# Power_Supply.net
KiCad netlist of a schematic drawn in Altium Designer
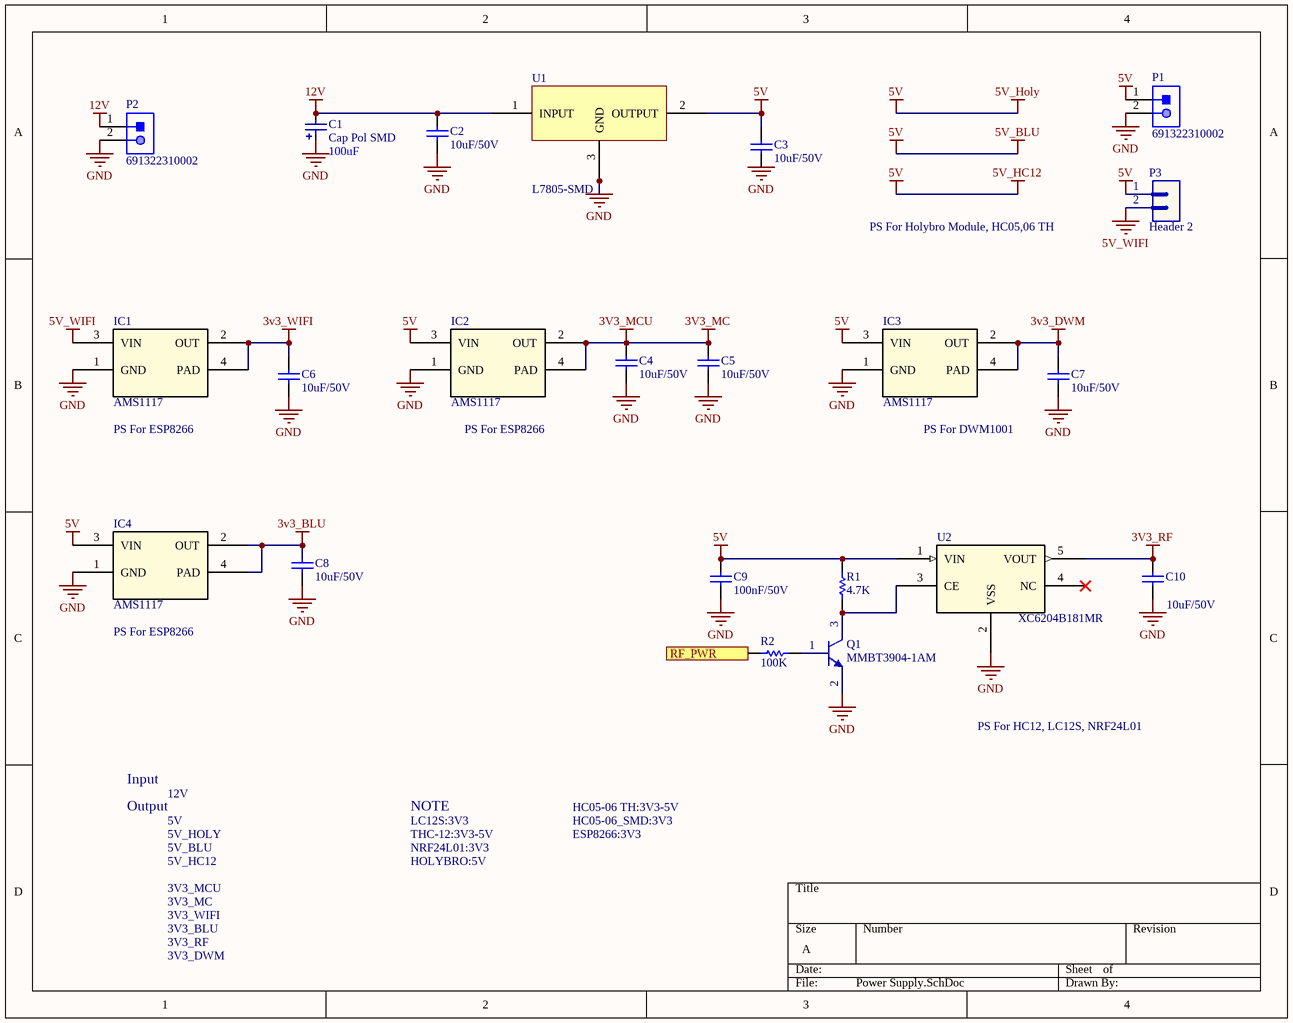
[diagram p0: Power Supply.SchDoc]

(export (version "E")
  (design (tool "Eeschema 10.0.6"))
  (components
    (comp (ref "C1")
      (value "Cap Pol SMD")
      (footprint "CAP ALU SIZE B")
      (description "Polarized Capacitor (Radial)")
      (fields (field (name "ALTIUM_VALUE") "100uF"))
      (libsource (lib "PIF_C16_lib") (part "Cap Pol SMD"))
    )
    (comp (ref "C2")
      (value "10uF/50V")
      (footprint "CAP-SM-0805")
      (description "CAP CER 10UF 50V X5R 0805")
      (fields
        (field (name "MANUFACTURER") "Yageo")
        (field (name "MANUFACTURER PART NUMBER") "CC0805KKX5R9BB106")
      )
      (libsource (lib "Capacitor") (part "Cap-10uF-50V-0805"))
    )
    (comp (ref "C3")
      (value "10uF/50V")
      (footprint "CAP-SM-0805")
      (description "CAP CER 10UF 50V X5R 0805")
      (fields
        (field (name "MANUFACTURER") "Yageo")
        (field (name "MANUFACTURER PART NUMBER") "CC0805KKX5R9BB106")
      )
      (libsource (lib "Capacitor") (part "Cap-10uF-50V-0805"))
    )
    (comp (ref "C4")
      (value "10uF/50V")
      (footprint "CAP-SM-0805")
      (description "CAP CER 10UF 50V X5R 0805")
      (fields
        (field (name "MANUFACTURER") "Yageo")
        (field (name "MANUFACTURER PART NUMBER") "CC0805KKX5R9BB106")
      )
      (libsource (lib "Capacitor") (part "Cap-10uF-50V-0805"))
    )
    (comp (ref "C5")
      (value "10uF/50V")
      (footprint "CAP-SM-0805")
      (description "CAP CER 10UF 50V X5R 0805")
      (fields
        (field (name "MANUFACTURER") "Yageo")
        (field (name "MANUFACTURER PART NUMBER") "CC0805KKX5R9BB106")
      )
      (libsource (lib "Capacitor") (part "Cap-10uF-50V-0805"))
    )
    (comp (ref "C6")
      (value "10uF/50V")
      (footprint "CAP-SM-0805")
      (description "CAP CER 10UF 50V X5R 0805")
      (fields
        (field (name "MANUFACTURER") "Yageo")
        (field (name "MANUFACTURER PART NUMBER") "CC0805KKX5R9BB106")
      )
      (libsource (lib "Capacitor") (part "Cap-10uF-50V-0805"))
    )
    (comp (ref "C7")
      (value "10uF/50V")
      (footprint "CAP-SM-0805")
      (description "CAP CER 10UF 50V X5R 0805")
      (fields
        (field (name "MANUFACTURER") "Yageo")
        (field (name "MANUFACTURER PART NUMBER") "CC0805KKX5R9BB106")
      )
      (libsource (lib "Capacitor") (part "Cap-10uF-50V-0805"))
    )
    (comp (ref "C8")
      (value "10uF/50V")
      (footprint "CAP-SM-0805")
      (description "CAP CER 10UF 50V X5R 0805")
      (fields
        (field (name "MANUFACTURER") "Yageo")
        (field (name "MANUFACTURER PART NUMBER") "CC0805KKX5R9BB106")
      )
      (libsource (lib "Capacitor") (part "Cap-10uF-50V-0805"))
    )
    (comp (ref "C9")
      (value "100nF/50V")
      (footprint "CAP-SM-0805")
      (description "CAP CER 0.1UF 50V Y5V 0805")
      (fields
        (field (name "MANUFACTURER") "Samsung Electro-Mechanics")
        (field (name "MANUFACTURER PART NUMBER") "CL21F104ZBCNNNC")
      )
      (libsource (lib "Capacitor") (part "Cap-100nF-50V-0805"))
    )
    (comp (ref "C10")
      (value "10uF/50V")
      (footprint "CAP-SM-0805")
      (description "CAP CER 10UF 50V X5R 0805")
      (fields
        (field (name "MANUFACTURER") "Yageo")
        (field (name "MANUFACTURER PART NUMBER") "CC0805KKX5R9BB106")
      )
      (libsource (lib "Capacitor") (part "Cap-10uF-50V-0805"))
    )
    (comp (ref "IC1")
      (value "AMS1117")
      (footprint "AMS1117")
      (fields (field (name "COPYRIGHT") "Copyright (C) 2018 Accelerated Designs. All rights reserved"))
      (libsource (lib "Integrated_Library") (part "AMS1117"))
    )
    (comp (ref "IC2")
      (value "AMS1117")
      (footprint "AMS1117")
      (fields (field (name "COPYRIGHT") "Copyright (C) 2018 Accelerated Designs. All rights reserved"))
      (libsource (lib "Integrated_Library") (part "AMS1117"))
    )
    (comp (ref "IC3")
      (value "AMS1117")
      (footprint "AMS1117")
      (fields (field (name "COPYRIGHT") "Copyright (C) 2018 Accelerated Designs. All rights reserved"))
      (libsource (lib "Integrated_Library") (part "AMS1117"))
    )
    (comp (ref "IC4")
      (value "AMS1117")
      (footprint "AMS1117")
      (fields (field (name "COPYRIGHT") "Copyright (C) 2018 Accelerated Designs. All rights reserved"))
      (libsource (lib "Integrated_Library") (part "AMS1117"))
    )
    (comp (ref "P1")
      (value "691322310002")
      (footprint "691322310002")
      (description "WR-TBL Serie 322 Horizontal PCB Header, Pluggable, pitch 3.81mm, 2p")
      (fields (field (name "PUBLISHER") "Wurth Elektronik"))
      (libsource (lib "691101710002_Altium_WR-TBL_rev19a") (part "691322310002"))
    )
    (comp (ref "P2")
      (value "691322310002")
      (footprint "691322310002")
      (description "WR-TBL Serie 322 Horizontal PCB Header, Pluggable, pitch 3.81mm, 2p")
      (fields (field (name "PUBLISHER") "Wurth Elektronik"))
      (libsource (lib "691101710002_Altium_WR-TBL_rev19a") (part "691322310002"))
    )
    (comp (ref "P3")
      (value "Header 2")
      (footprint "JP2")
      (description "Header, 2-Pin")
      (fields (field (name "PUBLISHER") "Altium Limited"))
      (libsource (lib "PIF_C16_lib") (part "Header 2"))
    )
    (comp (ref "Q1")
      (value "MMBT3904-1AM")
      (footprint "SOT23_NEX")
      (libsource (lib "BJT") (part "MMBT3904-1AM"))
    )
    (comp (ref "R1")
      (value "4.7K")
      (footprint "Resistor:RES-SM-0805")
      (description "RES 1K OHM 1% 1/4W 0805")
      (fields
        (field (name "MANUFACTURER") "Stackpole Electronics Inc")
        (field (name "MANUFACTURER PART NUMBER") "RNCP0805FTD1K00")
      )
      (libsource (lib "Resistor") (part "Res-1K-0805"))
    )
    (comp (ref "R2")
      (value "100K")
      (footprint "Resistor:RES-SM-0805")
      (description "RES 1K OHM 1% 1/4W 0805")
      (fields
        (field (name "MANUFACTURER") "Stackpole Electronics Inc")
        (field (name "MANUFACTURER PART NUMBER") "RNCP0805FTD1K00")
      )
      (libsource (lib "Resistor") (part "Res-1K-0805"))
    )
    (comp (ref "U1")
      (value "L7805-SMD")
      (footprint "L7805-SMD")
      (libsource (lib "Integrated_Library") (part "L7805-SMD"))
    )
    (comp (ref "U2")
      (value "XC6204B181MR")
      (footprint "XC6204B332MR")
      (fields (field (name "COPYRIGHT") "Copyright (C) 2018 Accelerated Designs. All rights reserved"))
      (libsource (lib "Integrated_Library") (part "XC6204B181MR"))
    )
  )
  (nets
    (net (code "1") (name "/RF_PWR") (class "Default")
      (node (ref "R2") (pin "2") (pinfunction "2_2") (pintype "passive"))
    )
    (net (code "2") (name "3V3_MC") (class "Default")
      (node (ref "C4") (pin "2") (pinfunction "2_2") (pintype "passive"))
      (node (ref "C5") (pin "2") (pinfunction "2_2") (pintype "passive"))
      (node (ref "IC2") (pin "2") (pinfunction "OUT_2") (pintype "open_collector"))
      (node (ref "IC2") (pin "4") (pinfunction "PAD_4") (pintype "power_in"))
    )
    (net (code "3") (name "3V3_RF") (class "Default")
      (node (ref "C10") (pin "2") (pinfunction "2_2") (pintype "passive"))
      (node (ref "U2") (pin "5") (pinfunction "VOUT_5") (pintype "output"))
    )
    (net (code "4") (name "3v3_BLU") (class "Default")
      (node (ref "C8") (pin "2") (pinfunction "2_2") (pintype "passive"))
      (node (ref "IC4") (pin "2") (pinfunction "OUT_2") (pintype "open_collector"))
      (node (ref "IC4") (pin "4") (pinfunction "PAD_4") (pintype "power_in"))
    )
    (net (code "5") (name "3v3_DWM") (class "Default")
      (node (ref "C7") (pin "2") (pinfunction "2_2") (pintype "passive"))
      (node (ref "IC3") (pin "2") (pinfunction "OUT_2") (pintype "open_collector"))
      (node (ref "IC3") (pin "4") (pinfunction "PAD_4") (pintype "power_in"))
    )
    (net (code "6") (name "3v3_WIFI") (class "Default")
      (node (ref "C6") (pin "2") (pinfunction "2_2") (pintype "passive"))
      (node (ref "IC1") (pin "2") (pinfunction "OUT_2") (pintype "open_collector"))
      (node (ref "IC1") (pin "4") (pinfunction "PAD_4") (pintype "power_in"))
    )
    (net (code "7") (name "5V") (class "Default")
      (node (ref "C3") (pin "2") (pinfunction "2_2") (pintype "passive"))
      (node (ref "C9") (pin "2") (pinfunction "2_2") (pintype "passive"))
      (node (ref "IC2") (pin "3") (pinfunction "VIN_3") (pintype "open_collector"))
      (node (ref "IC3") (pin "3") (pinfunction "VIN_3") (pintype "open_collector"))
      (node (ref "IC4") (pin "3") (pinfunction "VIN_3") (pintype "open_collector"))
      (node (ref "P1") (pin "1") (pinfunction "1_1") (pintype "passive"))
      (node (ref "P3") (pin "1") (pinfunction "1_1") (pintype "passive"))
      (node (ref "R1") (pin "2") (pinfunction "2_2") (pintype "passive"))
      (node (ref "U1") (pin "2") (pinfunction "OUTPUT_2") (pintype "passive"))
      (node (ref "U2") (pin "1") (pinfunction "VIN_1") (pintype "input"))
    )
    (net (code "8") (name "5V_WIFI") (class "Default")
      (node (ref "IC1") (pin "3") (pinfunction "VIN_3") (pintype "open_collector"))
      (node (ref "P3") (pin "2") (pinfunction "2_2") (pintype "passive"))
    )
    (net (code "9") (name "12V") (class "Default")
      (node (ref "C1") (pin "2") (pinfunction "2_2") (pintype "passive"))
      (node (ref "C2") (pin "2") (pinfunction "2_2") (pintype "passive"))
      (node (ref "P2") (pin "1") (pinfunction "1_1") (pintype "passive"))
      (node (ref "U1") (pin "1") (pinfunction "INPUT_1") (pintype "passive"))
    )
    (net (code "10") (name "GND") (class "Default")
      (node (ref "C1") (pin "1") (pinfunction "1_1") (pintype "passive"))
      (node (ref "C10") (pin "1") (pinfunction "1_1") (pintype "passive"))
      (node (ref "C2") (pin "1") (pinfunction "1_1") (pintype "passive"))
      (node (ref "C4") (pin "1") (pinfunction "1_1") (pintype "passive"))
      (node (ref "C5") (pin "1") (pinfunction "1_1") (pintype "passive"))
      (node (ref "C6") (pin "1") (pinfunction "1_1") (pintype "passive"))
      (node (ref "C7") (pin "1") (pinfunction "1_1") (pintype "passive"))
      (node (ref "C8") (pin "1") (pinfunction "1_1") (pintype "passive"))
      (node (ref "C9") (pin "1") (pinfunction "1_1") (pintype "passive"))
      (node (ref "IC1") (pin "1") (pinfunction "GND_1") (pintype "passive"))
      (node (ref "IC2") (pin "1") (pinfunction "GND_1") (pintype "passive"))
      (node (ref "IC3") (pin "1") (pinfunction "GND_1") (pintype "passive"))
      (node (ref "IC4") (pin "1") (pinfunction "GND_1") (pintype "passive"))
      (node (ref "P1") (pin "2") (pinfunction "2_2") (pintype "passive"))
      (node (ref "P2") (pin "2") (pinfunction "2_2") (pintype "passive"))
      (node (ref "Q1") (pin "2") (pinfunction "E_2") (pintype "passive"))
      (node (ref "U1") (pin "3") (pinfunction "GND_3") (pintype "passive"))
      (node (ref "U2") (pin "2") (pinfunction "VSS_2") (pintype "passive"))
    )
    (net (code "11") (name "Net-(Q1-B)") (class "Default")
      (node (ref "Q1") (pin "1") (pinfunction "B_1") (pintype "passive"))
      (node (ref "R2") (pin "1") (pinfunction "1_1") (pintype "passive"))
    )
    (net (code "12") (name "Net-(Q1-C)") (class "Default")
      (node (ref "Q1") (pin "3") (pinfunction "C_3") (pintype "passive"))
      (node (ref "R1") (pin "1") (pinfunction "1_1") (pintype "passive"))
      (node (ref "U2") (pin "3") (pinfunction "CE_3") (pintype "passive"))
    )
    (net (code "13") (name "unconnected-(C3-Pad1)") (class "Default")
      (node (ref "C3") (pin "1") (pinfunction "1_1") (pintype "passive"))
    )
    (net (code "14") (name "unconnected-(U2-NC-Pad4)") (class "Default")
      (node (ref "U2") (pin "4") (pinfunction "NC_4") (pintype "open_collector+no_connect"))
    )
  )
)
